# icp_dcs.net
KiCad netlist of a schematic drawn in EAGLE
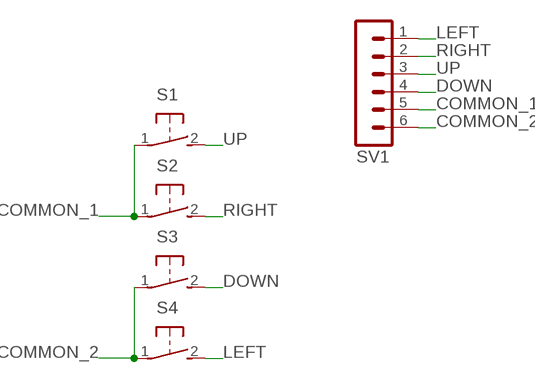
[diagram p0: schematic, sheet 1]

(export (version "E")
  (design (tool "Eeschema 10.0.6"))
  (components
    (comp (ref "S1")
      (value "31-XX")
      (footprint "eagle-import:B3F-31XX")
      (fields (field (name "MPN") "B3F-3100"))
      (libsource (lib "eagle-import") (part "31-XX"))
    )
    (comp (ref "S2")
      (value "31-XX")
      (footprint "eagle-import:B3F-31XX")
      (fields (field (name "MPN") "B3F-3100"))
      (libsource (lib "eagle-import") (part "31-XX"))
    )
    (comp (ref "S3")
      (value "31-XX")
      (footprint "eagle-import:B3F-31XX")
      (fields (field (name "MPN") "B3F-3100"))
      (libsource (lib "eagle-import") (part "31-XX"))
    )
    (comp (ref "S4")
      (value "31-XX")
      (footprint "eagle-import:B3F-31XX")
      (fields (field (name "MPN") "B3F-3100"))
      (libsource (lib "eagle-import") (part "31-XX"))
    )
    (comp (ref "SV1")
      (value "MA06-1")
      (footprint "eagle-import:MA06-1")
      (libsource (lib "eagle-import") (part "MA06-1"))
    )
  )
  (nets
    (net (code "1") (name "/COMMON_1") (class "Default")
      (node (ref "S1") (pin "1") (pinfunction "P_1") (pintype "passive"))
      (node (ref "S2") (pin "1") (pinfunction "P_1") (pintype "passive"))
      (node (ref "SV1") (pin "5") (pinfunction "5_5") (pintype "passive"))
    )
    (net (code "2") (name "/COMMON_2") (class "Default")
      (node (ref "S3") (pin "1") (pinfunction "P_1") (pintype "passive"))
      (node (ref "S4") (pin "1") (pinfunction "P_1") (pintype "passive"))
      (node (ref "SV1") (pin "6") (pinfunction "6_6") (pintype "passive"))
    )
    (net (code "3") (name "/DOWN") (class "Default")
      (node (ref "S3") (pin "2") (pinfunction "S_2") (pintype "passive"))
      (node (ref "SV1") (pin "4") (pinfunction "4_4") (pintype "passive"))
    )
    (net (code "4") (name "/LEFT") (class "Default")
      (node (ref "S4") (pin "2") (pinfunction "S_2") (pintype "passive"))
      (node (ref "SV1") (pin "1") (pinfunction "1_1") (pintype "passive"))
    )
    (net (code "5") (name "/RIGHT") (class "Default")
      (node (ref "S2") (pin "2") (pinfunction "S_2") (pintype "passive"))
      (node (ref "SV1") (pin "2") (pinfunction "2_2") (pintype "passive"))
    )
    (net (code "6") (name "/UP") (class "Default")
      (node (ref "S1") (pin "2") (pinfunction "S_2") (pintype "passive"))
      (node (ref "SV1") (pin "3") (pinfunction "3_3") (pintype "passive"))
    )
  )
)
